# TSOC_USBUART2.net
KiCad netlist of a schematic drawn in EAGLE
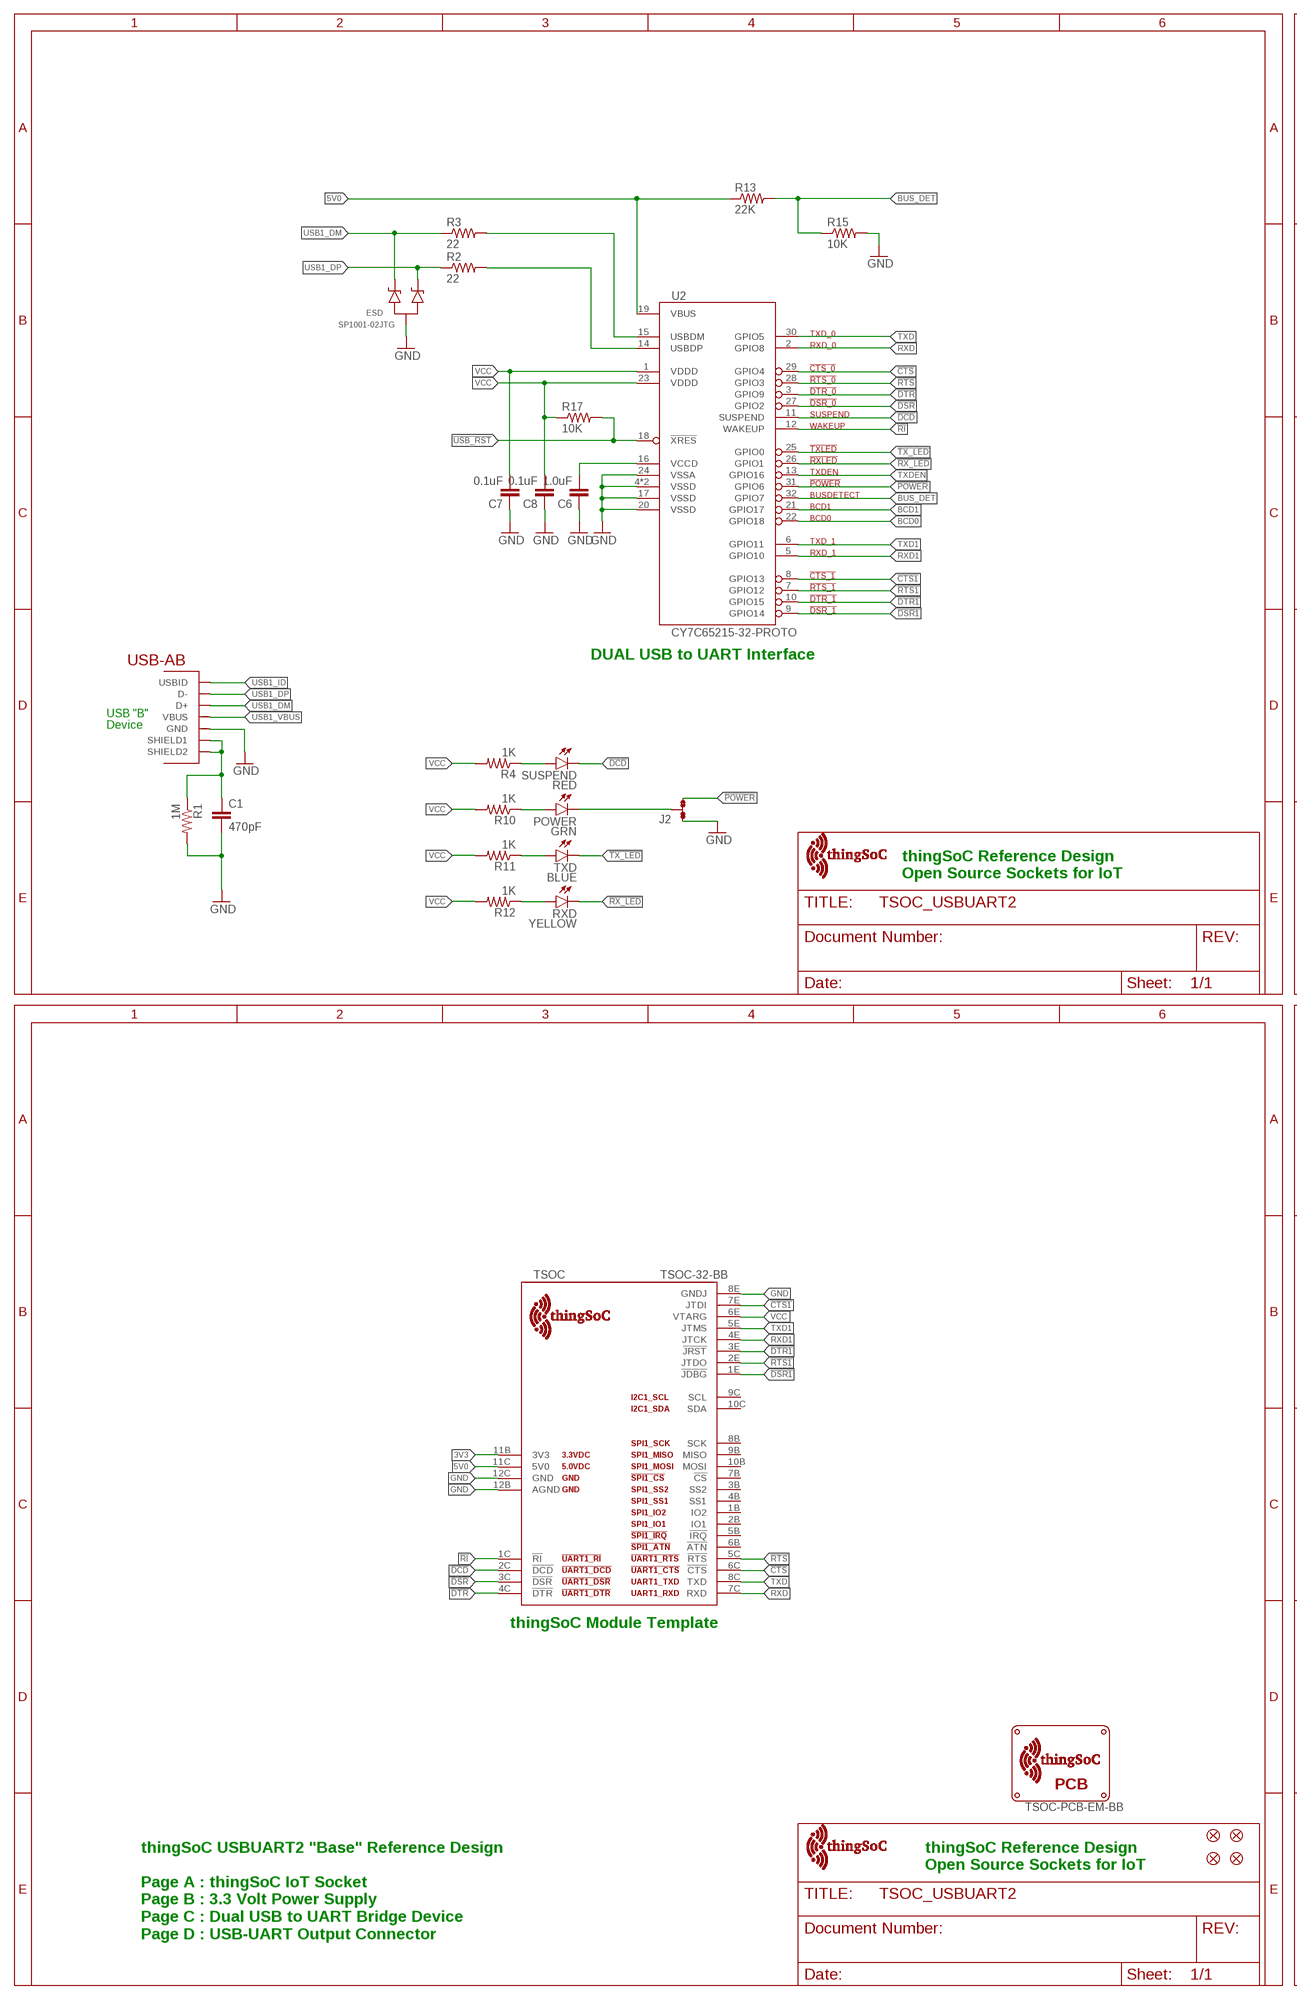
[diagram p0: schematic, sheet 1, part 1 of 2]
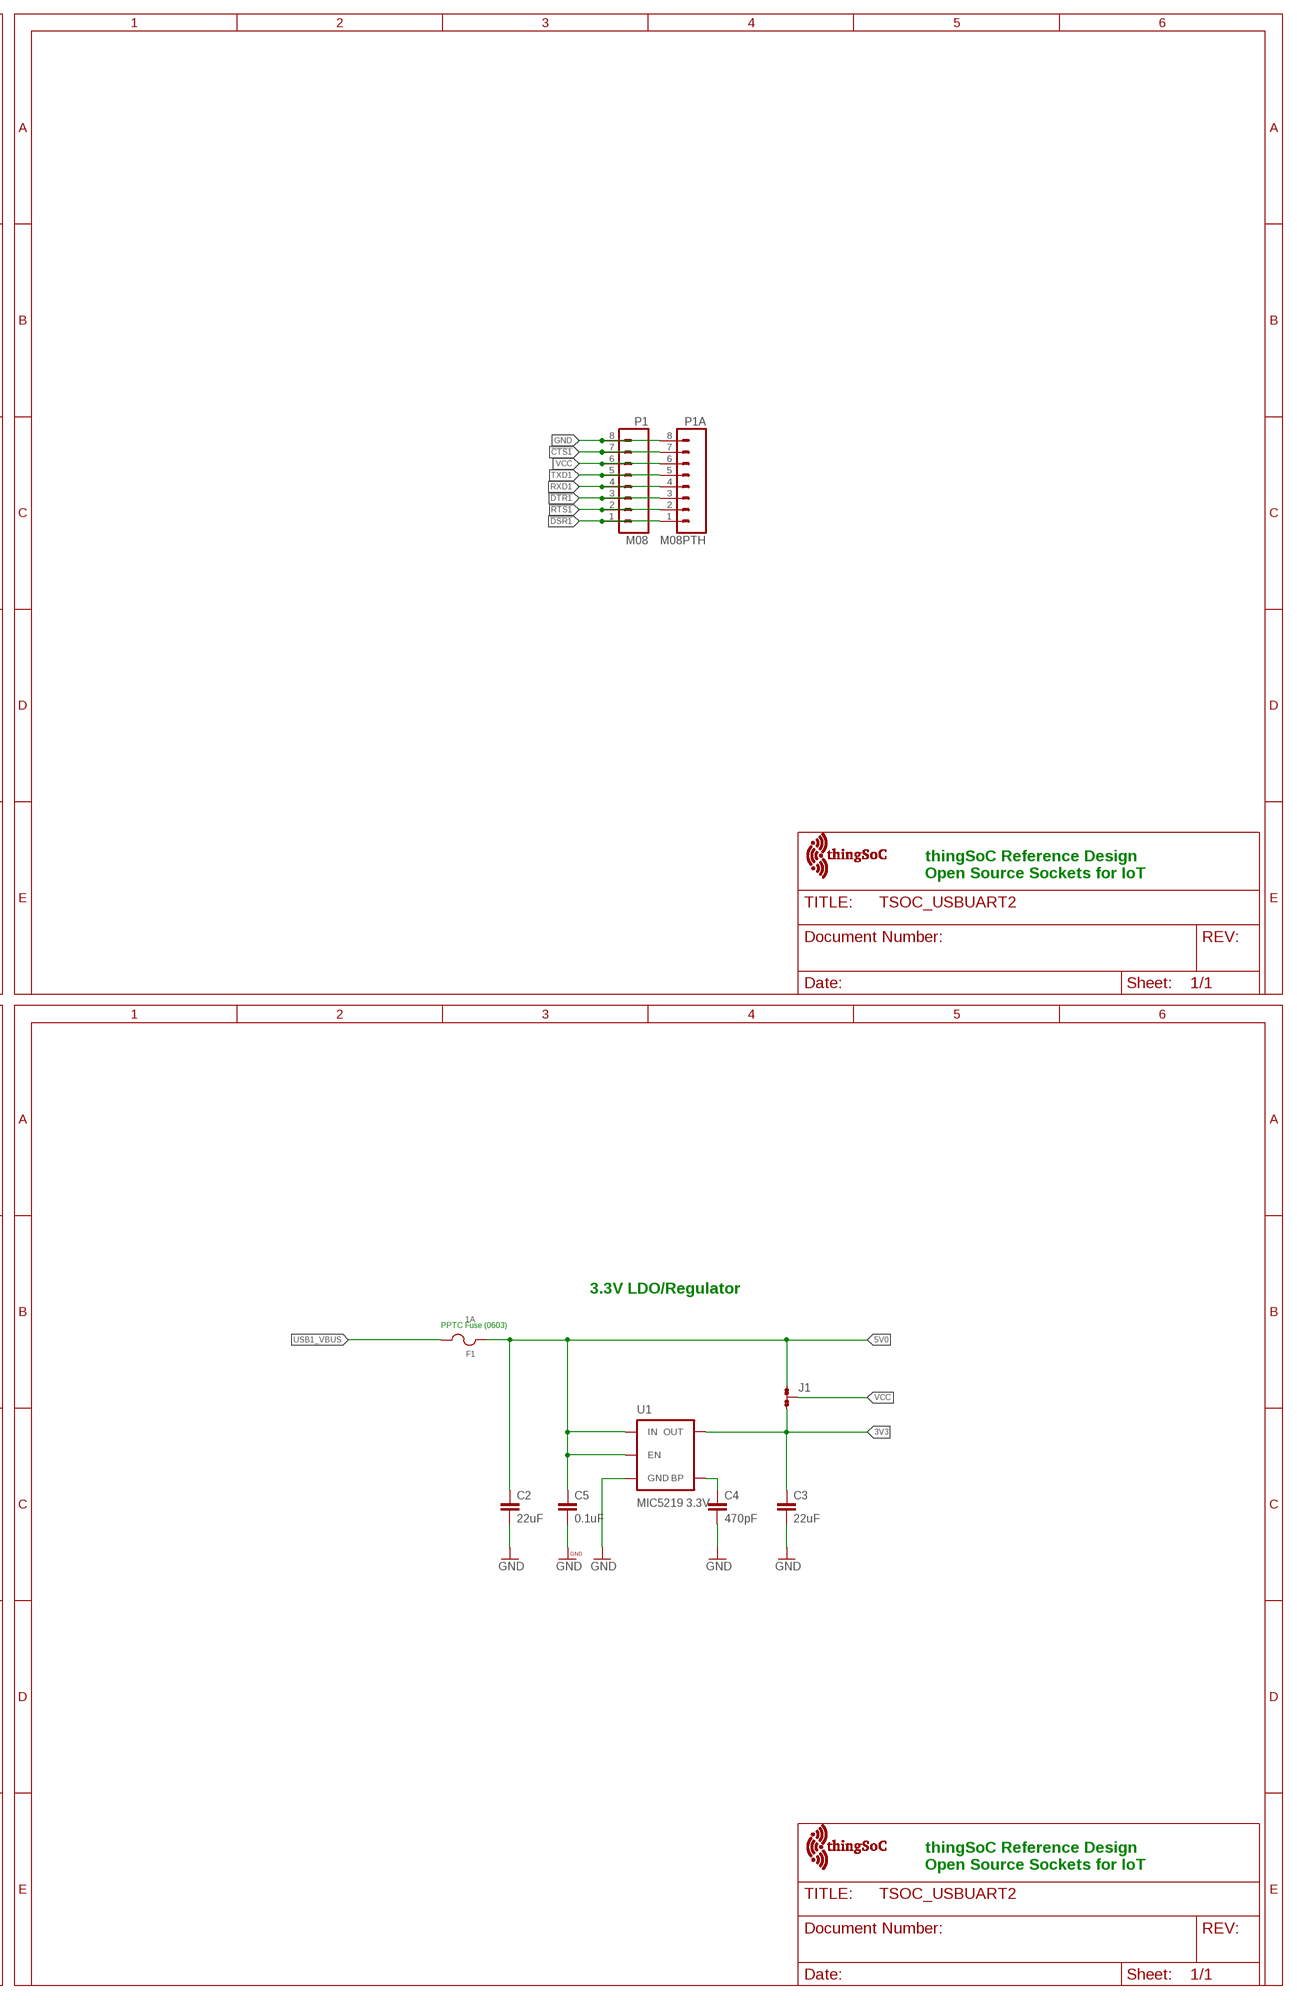
[diagram p1: schematic, sheet 1, part 2 of 2]

(export (version "E")
  (design (tool "Eeschema 10.0.6"))
  (components
    (comp (ref "C1")
      (value "470pF")
      (footprint "eagle-import:EIA-0603")
      (libsource (lib "eagle-import") (part "CAP-0603"))
    )
    (comp (ref "C2")
      (value "22uF")
      (footprint "eagle-import:EIA-1206")
      (libsource (lib "eagle-import") (part "CAP-1206"))
    )
    (comp (ref "C3")
      (value "22uF")
      (footprint "eagle-import:EIA-1206")
      (libsource (lib "eagle-import") (part "CAP-1206"))
    )
    (comp (ref "C4")
      (value "470pF")
      (footprint "eagle-import:EIA-0603")
      (libsource (lib "eagle-import") (part "CAP-0603"))
    )
    (comp (ref "C5")
      (value "0.1uF")
      (footprint "eagle-import:EIA-0603")
      (libsource (lib "eagle-import") (part "CAP-0603"))
    )
    (comp (ref "C6")
      (value "1.0uF")
      (footprint "eagle-import:EIA-0603")
      (libsource (lib "eagle-import") (part "CAP-0603"))
    )
    (comp (ref "C7")
      (value "0.1uF")
      (footprint "eagle-import:EIA-0603")
      (libsource (lib "eagle-import") (part "CAP-0603"))
    )
    (comp (ref "C8")
      (value "0.1uF")
      (footprint "eagle-import:EIA-0603")
      (libsource (lib "eagle-import") (part "CAP-0603"))
    )
    (comp (ref "ESD")
      (value "SP1001-02JTG")
      (footprint "eagle-import:SC70-3")
      (libsource (lib "eagle-import") (part "SP1001-02JTG"))
    )
    (comp (ref "F1")
      (value "1A")
      (footprint "eagle-import:EIA-0603")
      (libsource (lib "eagle-import") (part "FUSE"))
    )
    (comp (ref "FID1")
      (value "FIDUCIALUFIDUCIAL")
      (footprint "eagle-import:MICRO-FIDUCIAL")
      (libsource (lib "eagle-import") (part "FIDUCIALUFIDUCIAL"))
    )
    (comp (ref "FID2")
      (value "FIDUCIALUFIDUCIAL")
      (footprint "eagle-import:MICRO-FIDUCIAL")
      (libsource (lib "eagle-import") (part "FIDUCIALUFIDUCIAL"))
    )
    (comp (ref "FID3")
      (value "FIDUCIALUFIDUCIAL")
      (footprint "eagle-import:MICRO-FIDUCIAL")
      (libsource (lib "eagle-import") (part "FIDUCIALUFIDUCIAL"))
    )
    (comp (ref "FID4")
      (value "FIDUCIALUFIDUCIAL")
      (footprint "eagle-import:MICRO-FIDUCIAL")
      (libsource (lib "eagle-import") (part "FIDUCIALUFIDUCIAL"))
    )
    (comp (ref "J1")
      (value "JMP-3-1_2")
      (footprint "eagle-import:JMP-3-1_2")
      (libsource (lib "eagle-import") (part "JMP-3-1_2"))
    )
    (comp (ref "J2")
      (value "JMP-3-1_2")
      (footprint "eagle-import:JMP-3-1_2")
      (libsource (lib "eagle-import") (part "JMP-3-1_2"))
    )
    (comp (ref "P1")
      (value "M08")
      (footprint "eagle-import:1X08-SMD-FEMALE")
      (libsource (lib "eagle-import") (part "M08"))
    )
    (comp (ref "P1A")
      (value "M08PTH")
      (footprint "eagle-import:1X08")
      (libsource (lib "eagle-import") (part "M08PTH"))
    )
    (comp (ref "POWER")
      (value "GRN")
      (footprint "eagle-import:LED-0603")
      (libsource (lib "eagle-import") (part "LED0603"))
    )
    (comp (ref "R1")
      (value "1M")
      (footprint "eagle-import:EIA-0603")
      (libsource (lib "eagle-import") (part "RESISTOR-0603"))
    )
    (comp (ref "R2")
      (value "22")
      (footprint "eagle-import:EIA-0603")
      (libsource (lib "eagle-import") (part "RESISTOR-0603"))
    )
    (comp (ref "R3")
      (value "22")
      (footprint "eagle-import:EIA-0603")
      (libsource (lib "eagle-import") (part "RESISTOR-0603"))
    )
    (comp (ref "R4")
      (value "1K")
      (footprint "eagle-import:EIA-0603")
      (libsource (lib "eagle-import") (part "RESISTOR-0603"))
    )
    (comp (ref "R10")
      (value "1K")
      (footprint "eagle-import:EIA-0603")
      (libsource (lib "eagle-import") (part "RESISTOR-0603"))
    )
    (comp (ref "R11")
      (value "1K")
      (footprint "eagle-import:EIA-0603")
      (libsource (lib "eagle-import") (part "RESISTOR-0603"))
    )
    (comp (ref "R12")
      (value "1K")
      (footprint "eagle-import:EIA-0603")
      (libsource (lib "eagle-import") (part "RESISTOR-0603"))
    )
    (comp (ref "R13")
      (value "22K")
      (footprint "eagle-import:EIA-0603")
      (libsource (lib "eagle-import") (part "RESISTOR-0603"))
    )
    (comp (ref "R15")
      (value "10K")
      (footprint "eagle-import:EIA-0603")
      (libsource (lib "eagle-import") (part "RESISTOR-0603"))
    )
    (comp (ref "R17")
      (value "10K")
      (footprint "eagle-import:EIA-0603")
      (libsource (lib "eagle-import") (part "RESISTOR-0603"))
    )
    (comp (ref "RXD")
      (value "YELLOW")
      (footprint "eagle-import:LED-0603")
      (libsource (lib "eagle-import") (part "LED0603"))
    )
    (comp (ref "SUSPEND")
      (value "RED")
      (footprint "eagle-import:LED-0603")
      (libsource (lib "eagle-import") (part "LED0603"))
    )
    (comp (ref "TSOC")
      (value "TSOC-32-BB")
      (footprint "eagle-import:TSOC-BB-S32")
      (libsource (lib "eagle-import") (part "TSOC-32-BB"))
    )
    (comp (ref "TXD")
      (value "BLUE")
      (footprint "eagle-import:LED-0603")
      (libsource (lib "eagle-import") (part "LED0603"))
    )
    (comp (ref "U$1")
      (value "TSOC-PCB-EM-BB")
      (footprint "eagle-import:TSOC-EM-BB")
      (libsource (lib "eagle-import") (part "TSOC-PCB-EM-BB"))
    )
    (comp (ref "U$3")
      (value "TSOC-LOGO-LRG")
      (footprint "eagle-import:TSOC-LOGO-LRG")
      (libsource (lib "eagle-import") (part "TSOC-LOGO-LRG"))
    )
    (comp (ref "U$4")
      (value "TSOC-LOGO")
      (footprint "eagle-import:TSOC-LOGO-BLANK")
      (libsource (lib "eagle-import") (part "TSOC-LOGO"))
    )
    (comp (ref "U$5")
      (value "TSOC-LOGO")
      (footprint "eagle-import:TSOC-LOGO-BLANK")
      (libsource (lib "eagle-import") (part "TSOC-LOGO"))
    )
    (comp (ref "U$6")
      (value "TSOC-LOGO")
      (footprint "eagle-import:TSOC-LOGO-BLANK")
      (libsource (lib "eagle-import") (part "TSOC-LOGO"))
    )
    (comp (ref "U1")
      (value "MIC5219 3.3V")
      (footprint "eagle-import:SOT23-5")
      (libsource (lib "eagle-import") (part "V_REG_MIC52193.3V"))
    )
    (comp (ref "U2")
      (value "CY7C65215-32-PROTO")
      (footprint "eagle-import:QFN32-PROTO")
      (libsource (lib "eagle-import") (part "CY7C65215-32-PROTO"))
    )
    (comp (ref "USB")
      (value "USB_AB")
      (footprint "eagle-import:USB-AB-MICRO-SMD")
      (libsource (lib "eagle-import") (part "USB_AB"))
    )
  )
  (nets
    (net (code "1") (name "/~{CTS1}") (class "Default")
      (node (ref "P1") (pin "7") (pinfunction "7_7") (pintype "passive"))
      (node (ref "P1A") (pin "7") (pinfunction "7_7") (pintype "passive"))
      (node (ref "TSOC") (pin "7E") (pinfunction "JTDI_7E") (pintype "bidirectional"))
      (node (ref "U2") (pin "8") (pinfunction "GPIO13_8") (pintype "input"))
    )
    (net (code "2") (name "/~{CTS}") (class "Default")
      (node (ref "TSOC") (pin "6C") (pinfunction "~{CTS}_6C") (pintype "bidirectional"))
      (node (ref "U2") (pin "29") (pinfunction "GPIO4_29") (pintype "input"))
    )
    (net (code "3") (name "/~{DCD}") (class "Default")
      (node (ref "SUSPEND") (pin "C") (pinfunction "C_C") (pintype "passive"))
      (node (ref "TSOC") (pin "2C") (pinfunction "~{DCD}_2C") (pintype "bidirectional"))
      (node (ref "U2") (pin "11") (pinfunction "SUSPEND_11") (pintype "input"))
    )
    (net (code "4") (name "/~{DSR1}") (class "Default")
      (node (ref "P1") (pin "1") (pinfunction "1_1") (pintype "passive"))
      (node (ref "P1A") (pin "1") (pinfunction "1_1") (pintype "passive"))
      (node (ref "TSOC") (pin "1E") (pinfunction "~{JDBG}_1E") (pintype "bidirectional"))
      (node (ref "U2") (pin "9") (pinfunction "GPIO14_9") (pintype "input"))
    )
    (net (code "5") (name "/~{DSR}") (class "Default")
      (node (ref "TSOC") (pin "3C") (pinfunction "~{DSR}_3C") (pintype "bidirectional"))
      (node (ref "U2") (pin "27") (pinfunction "GPIO2_27") (pintype "input"))
    )
    (net (code "6") (name "/~{DTR1}") (class "Default")
      (node (ref "P1") (pin "3") (pinfunction "3_3") (pintype "passive"))
      (node (ref "P1A") (pin "3") (pinfunction "3_3") (pintype "passive"))
      (node (ref "TSOC") (pin "3E") (pinfunction "~{JRST}_3E") (pintype "bidirectional"))
      (node (ref "U2") (pin "10") (pinfunction "GPIO15_10") (pintype "output"))
    )
    (net (code "7") (name "/~{DTR}") (class "Default")
      (node (ref "TSOC") (pin "4C") (pinfunction "~{DTR}_4C") (pintype "bidirectional"))
      (node (ref "U2") (pin "3") (pinfunction "GPIO9_3") (pintype "output"))
    )
    (net (code "8") (name "/~{POWER}") (class "Default")
      (node (ref "J2") (pin "3") (pinfunction "3_3") (pintype "passive"))
      (node (ref "U2") (pin "31") (pinfunction "GPIO6_31") (pintype "input"))
    )
    (net (code "9") (name "/~{RI}") (class "Default")
      (node (ref "TSOC") (pin "1C") (pinfunction "~{RI}_1C") (pintype "bidirectional"))
      (node (ref "U2") (pin "12") (pinfunction "WAKEUP_12") (pintype "input"))
    )
    (net (code "10") (name "/~{RTS1}") (class "Default")
      (node (ref "P1") (pin "2") (pinfunction "2_2") (pintype "passive"))
      (node (ref "P1A") (pin "2") (pinfunction "2_2") (pintype "passive"))
      (node (ref "TSOC") (pin "2E") (pinfunction "JTDO_2E") (pintype "bidirectional"))
      (node (ref "U2") (pin "7") (pinfunction "GPIO12_7") (pintype "output"))
    )
    (net (code "11") (name "/~{RTS}") (class "Default")
      (node (ref "TSOC") (pin "5C") (pinfunction "~{RTS}_5C") (pintype "bidirectional"))
      (node (ref "U2") (pin "28") (pinfunction "GPIO3_28") (pintype "output"))
    )
    (net (code "12") (name "/~{RX_LED}") (class "Default")
      (node (ref "RXD") (pin "C") (pinfunction "C_C") (pintype "passive"))
      (node (ref "U2") (pin "26") (pinfunction "GPIO1_26") (pintype "input"))
    )
    (net (code "13") (name "/~{TX_LED}") (class "Default")
      (node (ref "TXD") (pin "C") (pinfunction "C_C") (pintype "passive"))
      (node (ref "U2") (pin "25") (pinfunction "GPIO0_25") (pintype "input"))
    )
    (net (code "14") (name "/~{USB_RST}") (class "Default")
      (node (ref "R17") (pin "2") (pinfunction "2_2") (pintype "passive"))
      (node (ref "U2") (pin "18") (pinfunction "~{XRES}_18") (pintype "input"))
    )
    (net (code "15") (name "3V3") (class "Default")
      (node (ref "C3") (pin "1") (pinfunction "1_1") (pintype "passive"))
      (node (ref "J1") (pin "3") (pinfunction "3_3") (pintype "passive"))
      (node (ref "TSOC") (pin "11B") (pinfunction "3V3_11B") (pintype "bidirectional"))
      (node (ref "U1") (pin "5") (pinfunction "OUT_5") (pintype "passive"))
    )
    (net (code "16") (name "5V0") (class "Default")
      (node (ref "C2") (pin "1") (pinfunction "1_1") (pintype "passive"))
      (node (ref "C5") (pin "1") (pinfunction "1_1") (pintype "passive"))
      (node (ref "F1") (pin "1") (pinfunction "P$1_1") (pintype "bidirectional"))
      (node (ref "J1") (pin "1") (pinfunction "1_1") (pintype "passive"))
      (node (ref "R13") (pin "1") (pinfunction "1_1") (pintype "passive"))
      (node (ref "TSOC") (pin "11C") (pinfunction "5V0_11C") (pintype "bidirectional"))
      (node (ref "U1") (pin "1") (pinfunction "IN_1") (pintype "input"))
      (node (ref "U1") (pin "3") (pinfunction "EN_3") (pintype "input"))
      (node (ref "U2") (pin "19") (pinfunction "VBUS_19") (pintype "power_in"))
    )
    (net (code "17") (name "BCD0") (class "Default")
      (node (ref "U2") (pin "22") (pinfunction "GPIO18_22") (pintype "input"))
    )
    (net (code "18") (name "BCD1") (class "Default")
      (node (ref "U2") (pin "21") (pinfunction "GPIO17_21") (pintype "input"))
    )
    (net (code "19") (name "BUS_DET") (class "Default")
      (node (ref "R13") (pin "2") (pinfunction "2_2") (pintype "passive"))
      (node (ref "R15") (pin "1") (pinfunction "1_1") (pintype "passive"))
      (node (ref "U2") (pin "32") (pinfunction "GPIO7_32") (pintype "input"))
    )
    (net (code "20") (name "GND") (class "Default")
      (node (ref "C1") (pin "2") (pinfunction "2_2") (pintype "passive"))
      (node (ref "C2") (pin "2") (pinfunction "2_2") (pintype "passive"))
      (node (ref "C3") (pin "2") (pinfunction "2_2") (pintype "passive"))
      (node (ref "C4") (pin "2") (pinfunction "2_2") (pintype "passive"))
      (node (ref "C5") (pin "2") (pinfunction "2_2") (pintype "passive"))
      (node (ref "C6") (pin "1") (pinfunction "1_1") (pintype "passive"))
      (node (ref "C7") (pin "1") (pinfunction "1_1") (pintype "passive"))
      (node (ref "C8") (pin "1") (pinfunction "1_1") (pintype "passive"))
      (node (ref "ESD") (pin "3") (pinfunction "A_3") (pintype "passive"))
      (node (ref "J2") (pin "1") (pinfunction "1_1") (pintype "passive"))
      (node (ref "P1") (pin "8") (pinfunction "8_8") (pintype "passive"))
      (node (ref "P1A") (pin "8") (pinfunction "8_8") (pintype "passive"))
      (node (ref "R1") (pin "2") (pinfunction "2_2") (pintype "passive"))
      (node (ref "R15") (pin "2") (pinfunction "2_2") (pintype "passive"))
      (node (ref "TSOC") (pin "12B") (pinfunction "AGND_12B") (pintype "bidirectional"))
      (node (ref "TSOC") (pin "12C") (pinfunction "GND_12C") (pintype "bidirectional"))
      (node (ref "TSOC") (pin "8E") (pinfunction "GNDJ_8E") (pintype "bidirectional"))
      (node (ref "U1") (pin "2") (pinfunction "GND_2") (pintype "input"))
      (node (ref "U2") (pin "17") (pinfunction "VSSD_17") (pintype "power_in"))
      (node (ref "U2") (pin "20") (pinfunction "VSSD_20") (pintype "power_in"))
      (node (ref "U2") (pin "24") (pinfunction "VSSA_24") (pintype "power_in"))
      (node (ref "U2") (pin "4") (pinfunction "VSSD_4") (pintype "power_in"))
      (node (ref "U2") (pin "EXP") (pinfunction "VSSD_EXP") (pintype "power_in"))
      (node (ref "USB") (pin "GND") (pinfunction "GND_GND") (pintype "bidirectional"))
    )
    (net (code "21") (name "Net-(C1-Pad1)") (class "Default")
      (node (ref "C1") (pin "1") (pinfunction "1_1") (pintype "passive"))
      (node (ref "R1") (pin "1") (pinfunction "1_1") (pintype "passive"))
      (node (ref "USB") (pin "SHIELD1") (pinfunction "SHIELD1_SHIELD1") (pintype "bidirectional"))
      (node (ref "USB") (pin "SHIELD2") (pinfunction "SHIELD2_SHIELD2") (pintype "bidirectional"))
    )
    (net (code "22") (name "Net-(J2-Pad2)") (class "Default")
      (node (ref "J2") (pin "2") (pinfunction "2_2") (pintype "passive"))
      (node (ref "POWER") (pin "C") (pinfunction "C_C") (pintype "passive"))
    )
    (net (code "23") (name "Net-(POWER-PadA)") (class "Default")
      (node (ref "POWER") (pin "A") (pinfunction "A_A") (pintype "passive"))
      (node (ref "R10") (pin "1") (pinfunction "1_1") (pintype "passive"))
    )
    (net (code "24") (name "Net-(R4-Pad1)") (class "Default")
      (node (ref "R4") (pin "1") (pinfunction "1_1") (pintype "passive"))
      (node (ref "SUSPEND") (pin "A") (pinfunction "A_A") (pintype "passive"))
    )
    (net (code "25") (name "Net-(R11-Pad1)") (class "Default")
      (node (ref "R11") (pin "1") (pinfunction "1_1") (pintype "passive"))
      (node (ref "TXD") (pin "A") (pinfunction "A_A") (pintype "passive"))
    )
    (net (code "26") (name "Net-(R12-Pad1)") (class "Default")
      (node (ref "R12") (pin "1") (pinfunction "1_1") (pintype "passive"))
      (node (ref "RXD") (pin "A") (pinfunction "A_A") (pintype "passive"))
    )
    (net (code "27") (name "Net-(U1-BP)") (class "Default")
      (node (ref "C4") (pin "1") (pinfunction "1_1") (pintype "passive"))
      (node (ref "U1") (pin "4") (pinfunction "BP_4") (pintype "input"))
    )
    (net (code "28") (name "Net-(U2-USBDM)") (class "Default")
      (node (ref "R3") (pin "2") (pinfunction "2_2") (pintype "passive"))
      (node (ref "U2") (pin "15") (pinfunction "USBDM_15") (pintype "bidirectional"))
    )
    (net (code "29") (name "Net-(U2-USBDP)") (class "Default")
      (node (ref "R2") (pin "2") (pinfunction "2_2") (pintype "passive"))
      (node (ref "U2") (pin "14") (pinfunction "USBDP_14") (pintype "bidirectional"))
    )
    (net (code "30") (name "Net-(U2-VCCD)") (class "Default")
      (node (ref "C6") (pin "2") (pinfunction "2_2") (pintype "passive"))
      (node (ref "U2") (pin "16") (pinfunction "VCCD_16") (pintype "output"))
    )
    (net (code "31") (name "RXD") (class "Default")
      (node (ref "TSOC") (pin "7C") (pinfunction "RXD_7C") (pintype "bidirectional"))
      (node (ref "U2") (pin "2") (pinfunction "GPIO8_2") (pintype "input"))
    )
    (net (code "32") (name "RXD1") (class "Default")
      (node (ref "P1") (pin "4") (pinfunction "4_4") (pintype "passive"))
      (node (ref "P1A") (pin "4") (pinfunction "4_4") (pintype "passive"))
      (node (ref "TSOC") (pin "4E") (pinfunction "JTCK_4E") (pintype "bidirectional"))
      (node (ref "U2") (pin "5") (pinfunction "GPIO10_5") (pintype "input"))
    )
    (net (code "33") (name "TXD") (class "Default")
      (node (ref "TSOC") (pin "8C") (pinfunction "TXD_8C") (pintype "bidirectional"))
      (node (ref "U2") (pin "30") (pinfunction "GPIO5_30") (pintype "output"))
    )
    (net (code "34") (name "TXD1") (class "Default")
      (node (ref "P1") (pin "5") (pinfunction "5_5") (pintype "passive"))
      (node (ref "P1A") (pin "5") (pinfunction "5_5") (pintype "passive"))
      (node (ref "TSOC") (pin "5E") (pinfunction "JTMS_5E") (pintype "bidirectional"))
      (node (ref "U2") (pin "6") (pinfunction "GPIO11_6") (pintype "output"))
    )
    (net (code "35") (name "TXDEN") (class "Default")
      (node (ref "U2") (pin "13") (pinfunction "GPIO16_13") (pintype "output"))
    )
    (net (code "36") (name "USB1_DM") (class "Default")
      (node (ref "ESD") (pin "2") (pinfunction "C2_2") (pintype "passive"))
      (node (ref "R3") (pin "1") (pinfunction "1_1") (pintype "passive"))
      (node (ref "USB") (pin "D+") (pinfunction "D+_D+") (pintype "bidirectional"))
    )
    (net (code "37") (name "USB1_DP") (class "Default")
      (node (ref "ESD") (pin "1") (pinfunction "C1_1") (pintype "passive"))
      (node (ref "R2") (pin "1") (pinfunction "1_1") (pintype "passive"))
      (node (ref "USB") (pin "D-") (pinfunction "D-_D-") (pintype "bidirectional"))
    )
    (net (code "38") (name "USB1_ID") (class "Default")
      (node (ref "USB") (pin "ID") (pinfunction "USBID_ID") (pintype "bidirectional"))
    )
    (net (code "39") (name "USB1_VBUS") (class "Default")
      (node (ref "F1") (pin "2") (pinfunction "P$2_2") (pintype "bidirectional"))
      (node (ref "USB") (pin "VBUS") (pinfunction "VBUS_VBUS") (pintype "bidirectional"))
    )
    (net (code "40") (name "VCC") (class "Default")
      (node (ref "C7") (pin "2") (pinfunction "2_2") (pintype "passive"))
      (node (ref "C8") (pin "2") (pinfunction "2_2") (pintype "passive"))
      (node (ref "J1") (pin "2") (pinfunction "2_2") (pintype "passive"))
      (node (ref "P1") (pin "6") (pinfunction "6_6") (pintype "passive"))
      (node (ref "P1A") (pin "6") (pinfunction "6_6") (pintype "passive"))
      (node (ref "R10") (pin "2") (pinfunction "2_2") (pintype "passive"))
      (node (ref "R11") (pin "2") (pinfunction "2_2") (pintype "passive"))
      (node (ref "R12") (pin "2") (pinfunction "2_2") (pintype "passive"))
      (node (ref "R17") (pin "1") (pinfunction "1_1") (pintype "passive"))
      (node (ref "R4") (pin "2") (pinfunction "2_2") (pintype "passive"))
      (node (ref "TSOC") (pin "6E") (pinfunction "VTARG_6E") (pintype "bidirectional"))
      (node (ref "U2") (pin "1") (pinfunction "VDDD_1") (pintype "power_in"))
      (node (ref "U2") (pin "23") (pinfunction "VDDD_23") (pintype "power_in"))
    )
    (net (code "41") (name "unconnected-(TSOC-IO1-Pad2B)") (class "Default")
      (node (ref "TSOC") (pin "2B") (pinfunction "IO1_2B") (pintype "bidirectional"))
    )
    (net (code "42") (name "unconnected-(TSOC-IO2-Pad1B)") (class "Default")
      (node (ref "TSOC") (pin "1B") (pinfunction "IO2_1B") (pintype "bidirectional"))
    )
    (net (code "43") (name "unconnected-(TSOC-MISO-Pad9B)") (class "Default")
      (node (ref "TSOC") (pin "9B") (pinfunction "MISO_9B") (pintype "bidirectional"))
    )
    (net (code "44") (name "unconnected-(TSOC-MOSI-Pad10B)") (class "Default")
      (node (ref "TSOC") (pin "10B") (pinfunction "MOSI_10B") (pintype "bidirectional"))
    )
    (net (code "45") (name "unconnected-(TSOC-SCK-Pad8B)") (class "Default")
      (node (ref "TSOC") (pin "8B") (pinfunction "SCK_8B") (pintype "bidirectional"))
    )
    (net (code "46") (name "unconnected-(TSOC-SCL-Pad9C)") (class "Default")
      (node (ref "TSOC") (pin "9C") (pinfunction "SCL_9C") (pintype "bidirectional"))
    )
    (net (code "47") (name "unconnected-(TSOC-SDA-Pad10C)") (class "Default")
      (node (ref "TSOC") (pin "10C") (pinfunction "SDA_10C") (pintype "bidirectional"))
    )
    (net (code "48") (name "unconnected-(TSOC-SS1-Pad4B)") (class "Default")
      (node (ref "TSOC") (pin "4B") (pinfunction "SS1_4B") (pintype "bidirectional"))
    )
    (net (code "49") (name "unconnected-(TSOC-SS2-Pad3B)") (class "Default")
      (node (ref "TSOC") (pin "3B") (pinfunction "SS2_3B") (pintype "bidirectional"))
    )
    (net (code "50") (name "unconnected-(TSOC-~{ATN}-Pad6B)") (class "Default")
      (node (ref "TSOC") (pin "6B") (pinfunction "~{ATN}_6B") (pintype "bidirectional"))
    )
    (net (code "51") (name "unconnected-(TSOC-~{CS}-Pad7B)") (class "Default")
      (node (ref "TSOC") (pin "7B") (pinfunction "~{CS}_7B") (pintype "bidirectional"))
    )
    (net (code "52") (name "unconnected-(TSOC-~{IRQ}-Pad5B)") (class "Default")
      (node (ref "TSOC") (pin "5B") (pinfunction "~{IRQ}_5B") (pintype "bidirectional"))
    )
  )
)
